# Sheet7.net
KiCad netlist of a schematic drawn in Altium Designer
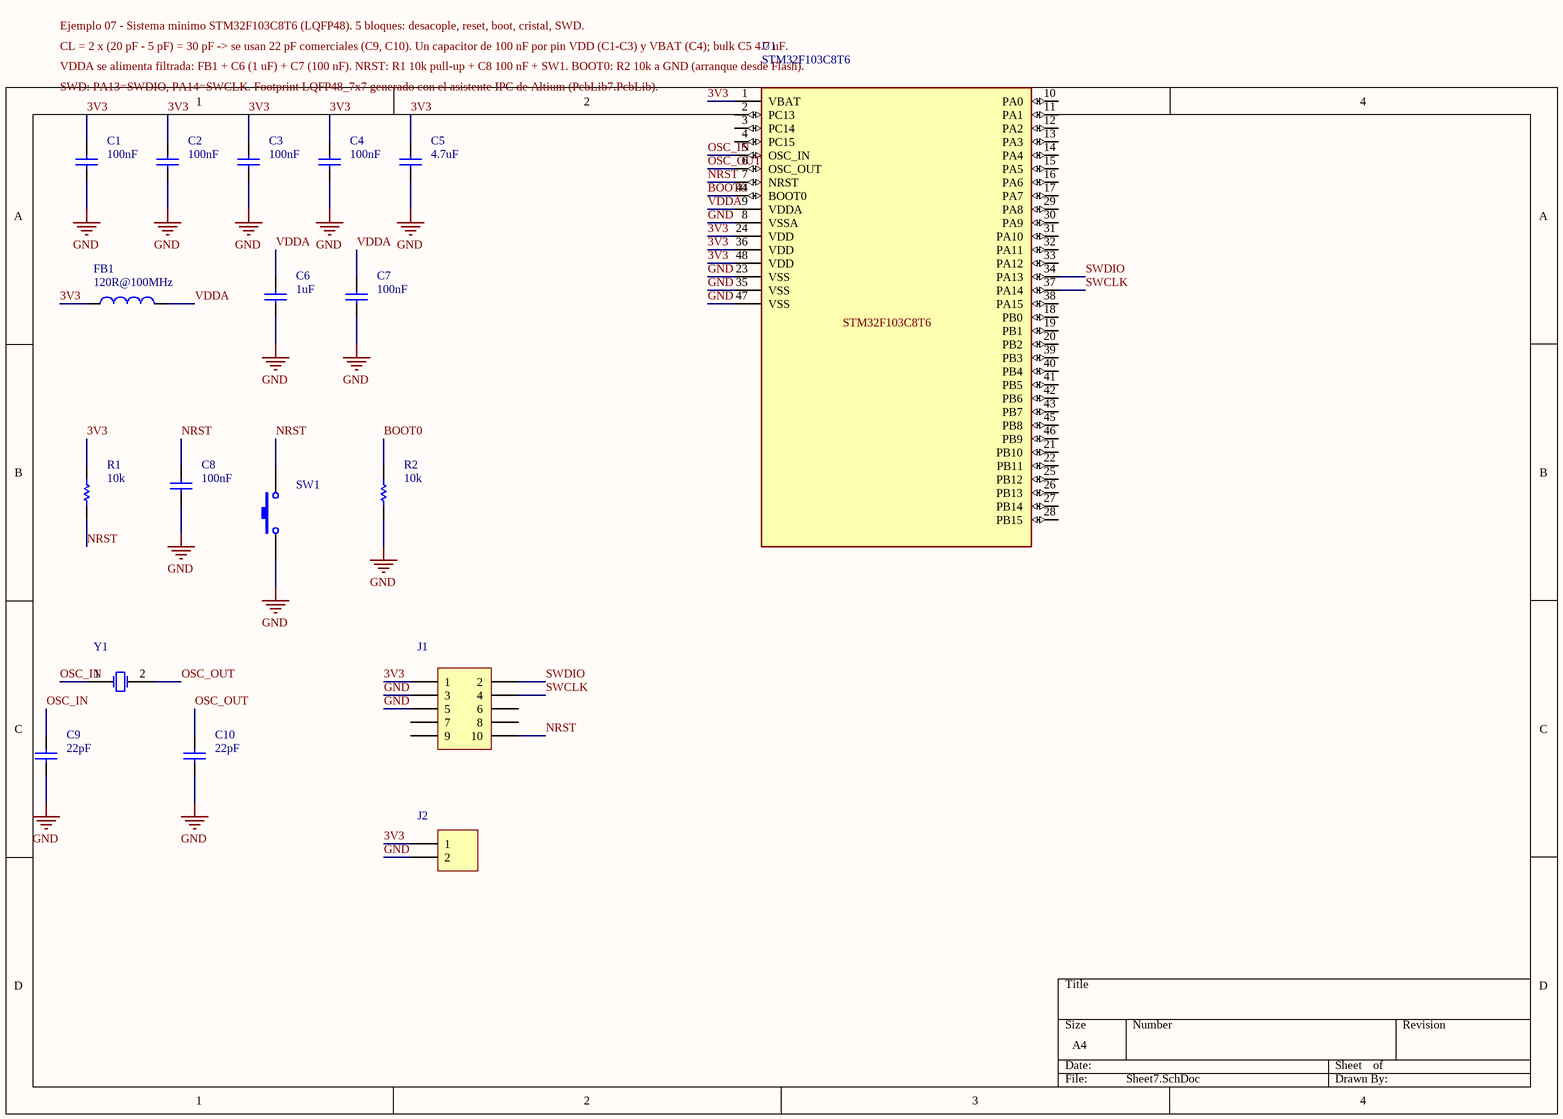
[diagram p0: Sheet7.SchDoc]

(export (version "E")
  (design (tool "Eeschema 10.0.6"))
  (components
    (comp (ref "C1")
      (value "100nF")
      (description "Capacitor 100 nF 0603 (desacople VDD/VBAT)")
      (fields
        (field (name "MANUFACTURER") "KEMET")
        (field (name "MANUFACTURER PART NUMBER") "C0603C104K5RACTU")
        (field (name "PUBLISHER") "Altium Limited")
      )
      (libsource (lib "Miscellaneous Devices") (part "Cap"))
    )
    (comp (ref "C2")
      (value "100nF")
      (description "Capacitor 100 nF 0603 (desacople VDD/VBAT)")
      (fields
        (field (name "MANUFACTURER") "KEMET")
        (field (name "MANUFACTURER PART NUMBER") "C0603C104K5RACTU")
        (field (name "PUBLISHER") "Altium Limited")
      )
      (libsource (lib "Miscellaneous Devices") (part "Cap"))
    )
    (comp (ref "C3")
      (value "100nF")
      (description "Capacitor 100 nF 0603 (desacople VDD/VBAT)")
      (fields
        (field (name "MANUFACTURER") "KEMET")
        (field (name "MANUFACTURER PART NUMBER") "C0603C104K5RACTU")
        (field (name "PUBLISHER") "Altium Limited")
      )
      (libsource (lib "Miscellaneous Devices") (part "Cap"))
    )
    (comp (ref "C4")
      (value "100nF")
      (description "Capacitor 100 nF 0603 (desacople VDD/VBAT)")
      (fields
        (field (name "MANUFACTURER") "KEMET")
        (field (name "MANUFACTURER PART NUMBER") "C0603C104K5RACTU")
        (field (name "PUBLISHER") "Altium Limited")
      )
      (libsource (lib "Miscellaneous Devices") (part "Cap"))
    )
    (comp (ref "C5")
      (value "4.7uF")
      (description "Capacitor 4.7 uF 0805 (bulk)")
      (fields
        (field (name "MANUFACTURER") "KEMET")
        (field (name "MANUFACTURER PART NUMBER") "C0805C475K8PACTU")
        (field (name "PUBLISHER") "Altium Limited")
      )
      (libsource (lib "Miscellaneous Devices") (part "Cap"))
    )
    (comp (ref "C6")
      (value "1uF")
      (description "Capacitor 1 uF 0603 (VDDA)")
      (fields
        (field (name "MANUFACTURER") "KEMET")
        (field (name "MANUFACTURER PART NUMBER") "C0603C105K8RACTU")
        (field (name "PUBLISHER") "Altium Limited")
      )
      (libsource (lib "Miscellaneous Devices") (part "Cap"))
    )
    (comp (ref "C7")
      (value "100nF")
      (description "Capacitor 100 nF 0603 (VDDA)")
      (fields
        (field (name "MANUFACTURER") "KEMET")
        (field (name "MANUFACTURER PART NUMBER") "C0603C104K5RACTU")
        (field (name "PUBLISHER") "Altium Limited")
      )
      (libsource (lib "Miscellaneous Devices") (part "Cap"))
    )
    (comp (ref "C8")
      (value "100nF")
      (description "Capacitor 100 nF 0603 (filtro NRST)")
      (fields
        (field (name "MANUFACTURER") "KEMET")
        (field (name "MANUFACTURER PART NUMBER") "C0603C104K5RACTU")
        (field (name "PUBLISHER") "Altium Limited")
      )
      (libsource (lib "Miscellaneous Devices") (part "Cap"))
    )
    (comp (ref "C9")
      (value "22pF")
      (description "Capacitor 22 pF 0603 (carga cristal)")
      (fields
        (field (name "MANUFACTURER") "KEMET")
        (field (name "MANUFACTURER PART NUMBER") "C0603C220J5GACTU")
        (field (name "PUBLISHER") "Altium Limited")
      )
      (libsource (lib "Miscellaneous Devices") (part "Cap"))
    )
    (comp (ref "C10")
      (value "22pF")
      (description "Capacitor 22 pF 0603 (carga cristal)")
      (fields
        (field (name "MANUFACTURER") "KEMET")
        (field (name "MANUFACTURER PART NUMBER") "C0603C220J5GACTU")
        (field (name "PUBLISHER") "Altium Limited")
      )
      (libsource (lib "Miscellaneous Devices") (part "Cap"))
    )
    (comp (ref "FB1")
      (value "120R@100MHz")
      (description "Ferrite bead 120 ohm @100 MHz 0603 (VDD -> VDDA)")
      (fields
        (field (name "MANUFACTURER") "Murata")
        (field (name "MANUFACTURER PART NUMBER") "BLM18PG121SN1D")
        (field (name "PUBLISHER") "Altium Limited")
      )
      (libsource (lib "Miscellaneous Devices") (part "Inductor"))
    )
    (comp (ref "J1")
      (value "Header 5X2")
      (description "Header 2x5 SWD: 3V3, SWDIO, SWCLK, GND, NRST")
      (fields
        (field (name "MANUFACTURER") "Generic")
        (field (name "MANUFACTURER PART NUMBER") "Pin header 2x5 2.54 mm")
        (field (name "PUBLISHER") "Altium Limited")
      )
      (libsource (lib "Miscellaneous Connectors") (part "Header 5X2"))
    )
    (comp (ref "J2")
      (value "Header 2")
      (description "Header 2 pin: alimentacion 3V3 y GND")
      (fields
        (field (name "MANUFACTURER") "Generic")
        (field (name "MANUFACTURER PART NUMBER") "Pin header 1x2")
        (field (name "PUBLISHER") "Altium Limited")
      )
      (libsource (lib "Miscellaneous Connectors") (part "Header 2"))
    )
    (comp (ref "R1")
      (value "10k")
      (description "Resistor 10 kohm 0603 (pull-up NRST)")
      (fields
        (field (name "MANUFACTURER") "Yageo")
        (field (name "MANUFACTURER PART NUMBER") "RC0603FR-0710KL")
        (field (name "PUBLISHER") "Altium Limited")
      )
      (libsource (lib "Miscellaneous Devices") (part "Res1"))
    )
    (comp (ref "R2")
      (value "10k")
      (description "Resistor 10 kohm 0603 (pull-down BOOT0)")
      (fields
        (field (name "MANUFACTURER") "Yageo")
        (field (name "MANUFACTURER PART NUMBER") "RC0603FR-0710KL")
        (field (name "PUBLISHER") "Altium Limited")
      )
      (libsource (lib "Miscellaneous Devices") (part "Res1"))
    )
    (comp (ref "SW1")
      (value "SW-PB")
      (description "Pulsador de reset")
      (fields
        (field (name "MANUFACTURER") "Generic")
        (field (name "MANUFACTURER PART NUMBER") "Tactile 6x6")
        (field (name "PUBLISHER") "Altium Limited")
      )
      (libsource (lib "Miscellaneous Devices") (part "SW-PB"))
    )
    (comp (ref "U1")
      (value "STM32F103C8T6")
      (footprint "LQFP48_7x7")
      (description "STM32F103C8T6 ARM Cortex-M3 72 MHz, 64 kB Flash, 20 kB RAM, LQFP48")
      (fields (field (name "MANUFACTURER") "STMicroelectronics"))
      (libsource (lib "*") (part "STM32F103C8T6"))
    )
    (comp (ref "Y1")
      (value "XTAL")
      (description "Crystal 8 MHz, CL=20 pF")
      (fields
        (field (name "MANUFACTURER") "Abracon")
        (field (name "MANUFACTURER PART NUMBER") "ABL-8.000MHZ-B2")
        (field (name "PUBLISHER") "Altium Limited")
      )
      (libsource (lib "Miscellaneous Devices") (part "XTAL"))
    )
  )
  (nets
    (net (code "1") (name "/3V3") (class "Default")
      (node (ref "C1") (pin "2") (pinfunction "2_2") (pintype "passive"))
      (node (ref "C2") (pin "2") (pinfunction "2_2") (pintype "passive"))
      (node (ref "C3") (pin "2") (pinfunction "2_2") (pintype "passive"))
      (node (ref "C4") (pin "2") (pinfunction "2_2") (pintype "passive"))
      (node (ref "C5") (pin "2") (pinfunction "2_2") (pintype "passive"))
      (node (ref "FB1") (pin "1") (pinfunction "1_1") (pintype "passive"))
      (node (ref "J1") (pin "1") (pinfunction "1_1") (pintype "passive"))
      (node (ref "J2") (pin "1") (pinfunction "1_1") (pintype "passive"))
      (node (ref "R1") (pin "2") (pinfunction "2_2") (pintype "passive"))
      (node (ref "U1") (pin "1") (pinfunction "VBAT_1") (pintype "power_in"))
      (node (ref "U1") (pin "24") (pinfunction "VDD_24") (pintype "power_in"))
      (node (ref "U1") (pin "36") (pinfunction "VDD_36") (pintype "power_in"))
      (node (ref "U1") (pin "48") (pinfunction "VDD_48") (pintype "power_in"))
    )
    (net (code "2") (name "/BOOT0") (class "Default")
      (node (ref "R2") (pin "2") (pinfunction "2_2") (pintype "passive"))
      (node (ref "U1") (pin "44") (pinfunction "BOOT0_44") (pintype "bidirectional"))
    )
    (net (code "3") (name "/NRST") (class "Default")
      (node (ref "C8") (pin "2") (pinfunction "2_2") (pintype "passive"))
      (node (ref "J1") (pin "10") (pinfunction "10_10") (pintype "passive"))
      (node (ref "R1") (pin "1") (pinfunction "1_1") (pintype "passive"))
      (node (ref "SW1") (pin "2") (pinfunction "2_2") (pintype "passive"))
      (node (ref "U1") (pin "7") (pinfunction "NRST_7") (pintype "bidirectional"))
    )
    (net (code "4") (name "/OSC_IN") (class "Default")
      (node (ref "C9") (pin "2") (pinfunction "2_2") (pintype "passive"))
      (node (ref "U1") (pin "5") (pinfunction "OSC_IN_5") (pintype "bidirectional"))
      (node (ref "Y1") (pin "1") (pinfunction "OSC1_1") (pintype "passive"))
    )
    (net (code "5") (name "/OSC_OUT") (class "Default")
      (node (ref "C10") (pin "2") (pinfunction "2_2") (pintype "passive"))
      (node (ref "U1") (pin "6") (pinfunction "OSC_OUT_6") (pintype "bidirectional"))
      (node (ref "Y1") (pin "2") (pinfunction "OSC2_2") (pintype "passive"))
    )
    (net (code "6") (name "/SWCLK") (class "Default")
      (node (ref "J1") (pin "4") (pinfunction "4_4") (pintype "passive"))
      (node (ref "U1") (pin "37") (pinfunction "PA14_37") (pintype "bidirectional"))
    )
    (net (code "7") (name "/SWDIO") (class "Default")
      (node (ref "J1") (pin "2") (pinfunction "2_2") (pintype "passive"))
      (node (ref "U1") (pin "34") (pinfunction "PA13_34") (pintype "bidirectional"))
    )
    (net (code "8") (name "/VDDA") (class "Default")
      (node (ref "C6") (pin "2") (pinfunction "2_2") (pintype "passive"))
      (node (ref "C7") (pin "2") (pinfunction "2_2") (pintype "passive"))
      (node (ref "FB1") (pin "2") (pinfunction "2_2") (pintype "passive"))
      (node (ref "U1") (pin "9") (pinfunction "VDDA_9") (pintype "power_in"))
    )
    (net (code "9") (name "GND") (class "Default")
      (node (ref "C1") (pin "1") (pinfunction "1_1") (pintype "passive"))
      (node (ref "C10") (pin "1") (pinfunction "1_1") (pintype "passive"))
      (node (ref "C2") (pin "1") (pinfunction "1_1") (pintype "passive"))
      (node (ref "C3") (pin "1") (pinfunction "1_1") (pintype "passive"))
      (node (ref "C4") (pin "1") (pinfunction "1_1") (pintype "passive"))
      (node (ref "C5") (pin "1") (pinfunction "1_1") (pintype "passive"))
      (node (ref "C6") (pin "1") (pinfunction "1_1") (pintype "passive"))
      (node (ref "C7") (pin "1") (pinfunction "1_1") (pintype "passive"))
      (node (ref "C8") (pin "1") (pinfunction "1_1") (pintype "passive"))
      (node (ref "C9") (pin "1") (pinfunction "1_1") (pintype "passive"))
      (node (ref "J1") (pin "3") (pinfunction "3_3") (pintype "passive"))
      (node (ref "J1") (pin "5") (pinfunction "5_5") (pintype "passive"))
      (node (ref "J2") (pin "2") (pinfunction "2_2") (pintype "passive"))
      (node (ref "R2") (pin "1") (pinfunction "1_1") (pintype "passive"))
      (node (ref "SW1") (pin "1") (pinfunction "1_1") (pintype "passive"))
      (node (ref "U1") (pin "23") (pinfunction "VSS_23") (pintype "power_in"))
      (node (ref "U1") (pin "35") (pinfunction "VSS_35") (pintype "power_in"))
      (node (ref "U1") (pin "47") (pinfunction "VSS_47") (pintype "power_in"))
      (node (ref "U1") (pin "8") (pinfunction "VSSA_8") (pintype "power_in"))
    )
    (net (code "10") (name "unconnected-(J1-Pad6)") (class "Default")
      (node (ref "J1") (pin "6") (pinfunction "6_6") (pintype "passive"))
    )
    (net (code "11") (name "unconnected-(J1-Pad7)") (class "Default")
      (node (ref "J1") (pin "7") (pinfunction "7_7") (pintype "passive"))
    )
    (net (code "12") (name "unconnected-(J1-Pad8)") (class "Default")
      (node (ref "J1") (pin "8") (pinfunction "8_8") (pintype "passive"))
    )
    (net (code "13") (name "unconnected-(J1-Pad9)") (class "Default")
      (node (ref "J1") (pin "9") (pinfunction "9_9") (pintype "passive"))
    )
    (net (code "14") (name "unconnected-(U1-PA0-Pad10)") (class "Default")
      (node (ref "U1") (pin "10") (pinfunction "PA0_10") (pintype "bidirectional"))
    )
    (net (code "15") (name "unconnected-(U1-PA1-Pad11)") (class "Default")
      (node (ref "U1") (pin "11") (pinfunction "PA1_11") (pintype "bidirectional"))
    )
    (net (code "16") (name "unconnected-(U1-PA2-Pad12)") (class "Default")
      (node (ref "U1") (pin "12") (pinfunction "PA2_12") (pintype "bidirectional"))
    )
    (net (code "17") (name "unconnected-(U1-PA3-Pad13)") (class "Default")
      (node (ref "U1") (pin "13") (pinfunction "PA3_13") (pintype "bidirectional"))
    )
    (net (code "18") (name "unconnected-(U1-PA4-Pad14)") (class "Default")
      (node (ref "U1") (pin "14") (pinfunction "PA4_14") (pintype "bidirectional"))
    )
    (net (code "19") (name "unconnected-(U1-PA5-Pad15)") (class "Default")
      (node (ref "U1") (pin "15") (pinfunction "PA5_15") (pintype "bidirectional"))
    )
    (net (code "20") (name "unconnected-(U1-PA6-Pad16)") (class "Default")
      (node (ref "U1") (pin "16") (pinfunction "PA6_16") (pintype "bidirectional"))
    )
    (net (code "21") (name "unconnected-(U1-PA7-Pad17)") (class "Default")
      (node (ref "U1") (pin "17") (pinfunction "PA7_17") (pintype "bidirectional"))
    )
    (net (code "22") (name "unconnected-(U1-PA8-Pad29)") (class "Default")
      (node (ref "U1") (pin "29") (pinfunction "PA8_29") (pintype "bidirectional"))
    )
    (net (code "23") (name "unconnected-(U1-PA9-Pad30)") (class "Default")
      (node (ref "U1") (pin "30") (pinfunction "PA9_30") (pintype "bidirectional"))
    )
    (net (code "24") (name "unconnected-(U1-PA10-Pad31)") (class "Default")
      (node (ref "U1") (pin "31") (pinfunction "PA10_31") (pintype "bidirectional"))
    )
    (net (code "25") (name "unconnected-(U1-PA11-Pad32)") (class "Default")
      (node (ref "U1") (pin "32") (pinfunction "PA11_32") (pintype "bidirectional"))
    )
    (net (code "26") (name "unconnected-(U1-PA12-Pad33)") (class "Default")
      (node (ref "U1") (pin "33") (pinfunction "PA12_33") (pintype "bidirectional"))
    )
    (net (code "27") (name "unconnected-(U1-PA15-Pad38)") (class "Default")
      (node (ref "U1") (pin "38") (pinfunction "PA15_38") (pintype "bidirectional"))
    )
    (net (code "28") (name "unconnected-(U1-PB0-Pad18)") (class "Default")
      (node (ref "U1") (pin "18") (pinfunction "PB0_18") (pintype "bidirectional"))
    )
    (net (code "29") (name "unconnected-(U1-PB1-Pad19)") (class "Default")
      (node (ref "U1") (pin "19") (pinfunction "PB1_19") (pintype "bidirectional"))
    )
    (net (code "30") (name "unconnected-(U1-PB2-Pad20)") (class "Default")
      (node (ref "U1") (pin "20") (pinfunction "PB2_20") (pintype "bidirectional"))
    )
    (net (code "31") (name "unconnected-(U1-PB3-Pad39)") (class "Default")
      (node (ref "U1") (pin "39") (pinfunction "PB3_39") (pintype "bidirectional"))
    )
    (net (code "32") (name "unconnected-(U1-PB4-Pad40)") (class "Default")
      (node (ref "U1") (pin "40") (pinfunction "PB4_40") (pintype "bidirectional"))
    )
    (net (code "33") (name "unconnected-(U1-PB5-Pad41)") (class "Default")
      (node (ref "U1") (pin "41") (pinfunction "PB5_41") (pintype "bidirectional"))
    )
    (net (code "34") (name "unconnected-(U1-PB6-Pad42)") (class "Default")
      (node (ref "U1") (pin "42") (pinfunction "PB6_42") (pintype "bidirectional"))
    )
    (net (code "35") (name "unconnected-(U1-PB7-Pad43)") (class "Default")
      (node (ref "U1") (pin "43") (pinfunction "PB7_43") (pintype "bidirectional"))
    )
    (net (code "36") (name "unconnected-(U1-PB8-Pad45)") (class "Default")
      (node (ref "U1") (pin "45") (pinfunction "PB8_45") (pintype "bidirectional"))
    )
    (net (code "37") (name "unconnected-(U1-PB9-Pad46)") (class "Default")
      (node (ref "U1") (pin "46") (pinfunction "PB9_46") (pintype "bidirectional"))
    )
    (net (code "38") (name "unconnected-(U1-PB10-Pad21)") (class "Default")
      (node (ref "U1") (pin "21") (pinfunction "PB10_21") (pintype "bidirectional"))
    )
    (net (code "39") (name "unconnected-(U1-PB11-Pad22)") (class "Default")
      (node (ref "U1") (pin "22") (pinfunction "PB11_22") (pintype "bidirectional"))
    )
    (net (code "40") (name "unconnected-(U1-PB12-Pad25)") (class "Default")
      (node (ref "U1") (pin "25") (pinfunction "PB12_25") (pintype "bidirectional"))
    )
    (net (code "41") (name "unconnected-(U1-PB13-Pad26)") (class "Default")
      (node (ref "U1") (pin "26") (pinfunction "PB13_26") (pintype "bidirectional"))
    )
    (net (code "42") (name "unconnected-(U1-PB14-Pad27)") (class "Default")
      (node (ref "U1") (pin "27") (pinfunction "PB14_27") (pintype "bidirectional"))
    )
    (net (code "43") (name "unconnected-(U1-PB15-Pad28)") (class "Default")
      (node (ref "U1") (pin "28") (pinfunction "PB15_28") (pintype "bidirectional"))
    )
    (net (code "44") (name "unconnected-(U1-PC13-Pad2)") (class "Default")
      (node (ref "U1") (pin "2") (pinfunction "PC13_2") (pintype "bidirectional"))
    )
    (net (code "45") (name "unconnected-(U1-PC14-Pad3)") (class "Default")
      (node (ref "U1") (pin "3") (pinfunction "PC14_3") (pintype "bidirectional"))
    )
    (net (code "46") (name "unconnected-(U1-PC15-Pad4)") (class "Default")
      (node (ref "U1") (pin "4") (pinfunction "PC15_4") (pintype "bidirectional"))
    )
  )
)
